# design.net
KiCad netlist of a schematic drawn in Altium Designer
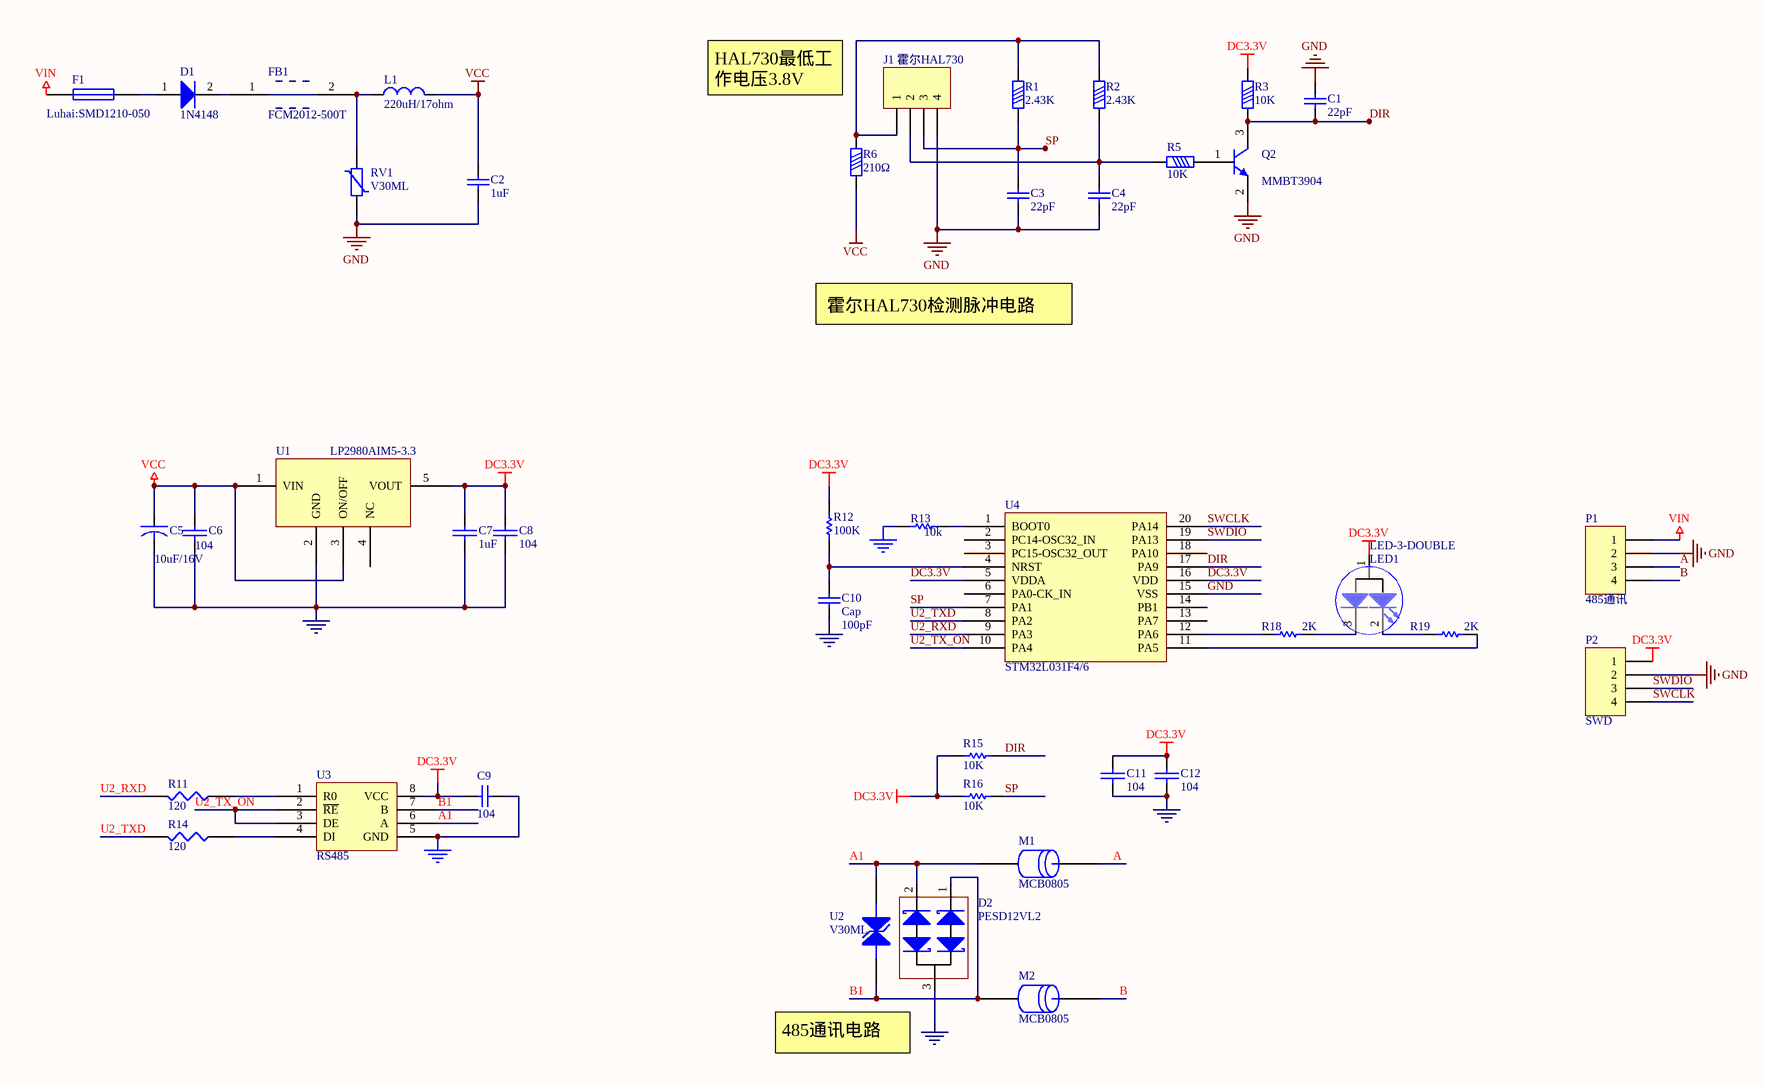
[diagram p0: 二合一正反转(改).SchDoc]

(export (version "E")
  (design (tool "Eeschema 10.0.6"))
  (components
    (comp (ref "C1")
      (value "22pF")
      (footprint "0603C")
      (description "Polarized Capacitor (Radial)")
      (fields (field (name "Comment") "Cap Chip 0603") (field (name "PUBLISHER") "Altium Limited"))
      (libsource (lib "EButterflyIntegratedLibrary") (part "Cap Chip 0603"))
    )
    (comp (ref "C2")
      (value "1uF")
      (footprint "0805C")
      (description "Polarized Capacitor (Radial)")
      (fields (field (name "PUBLISHER") "Altium Limited"))
      (libsource (lib "EButterflyIntegratedLibrary") (part "Cap Chip 0805"))
    )
    (comp (ref "C3")
      (value "22pF")
      (footprint "0603C")
      (description "Polarized Capacitor (Radial)")
      (fields (field (name "Comment") "Cap Chip 0603") (field (name "PUBLISHER") "Altium Limited"))
      (libsource (lib "EButterflyIntegratedLibrary") (part "Cap Chip 0603"))
    )
    (comp (ref "C4")
      (value "22pF")
      (footprint "0603C")
      (description "Polarized Capacitor (Radial)")
      (fields (field (name "Comment") "Cap Chip 0603") (field (name "PUBLISHER") "Altium Limited"))
      (libsource (lib "EButterflyIntegratedLibrary") (part "Cap Chip 0603"))
    )
    (comp (ref "C5")
      (value "10uF/16V")
      (footprint "A3216")
      (description "Capacitor")
      (libsource (lib "*") (part "CAPACITOR"))
    )
    (comp (ref "C6")
      (value "104")
      (footprint "0603C")
      (description "Capacitor")
      (libsource (lib "*") (part "CAP"))
    )
    (comp (ref "C7")
      (value "1uF")
      (footprint "0603C")
      (description "Capacitor")
      (libsource (lib "*") (part "CAP"))
    )
    (comp (ref "C8")
      (value "104")
      (footprint "0603C")
      (description "Capacitor")
      (libsource (lib "*") (part "CAP"))
    )
    (comp (ref "C9")
      (value "104")
      (footprint "0603C")
      (description "Capacitor")
      (fields (field (name "PUBLISHER") "*"))
      (libsource (lib "*") (part "Cap"))
    )
    (comp (ref "C10")
      (value "Cap")
      (footprint "0603C")
      (description "Capacitor")
      (fields (field (name "ALTIUM_VALUE") "100pF") (field (name "PUBLISHER") "Altium Limited"))
      (libsource (lib "Miscellaneous Devices") (part "Cap"))
    )
    (comp (ref "C11")
      (value "104")
      (footprint "0603C")
      (description "Capacitor")
      (libsource (lib "*") (part "CAP"))
    )
    (comp (ref "C12")
      (value "104")
      (footprint "0603C")
      (description "Capacitor")
      (libsource (lib "*") (part "CAP"))
    )
    (comp (ref "D1")
      (value "1N4148")
      (footprint "1N4148")
      (libsource (lib "Integrated_Library1") (part "1N4148"))
    )
    (comp (ref "D2") (value "PESD12VL2") (footprint "SOT23") (libsource (lib "lewis lib") (part "TVS")))
    (comp (ref "F1")
      (value "Luhai:SMD1210-050")
      (footprint "1210R")
      (description "Fuse")
      (fields (field (name "PUBLISHER") "Altium Limited"))
      (libsource (lib "Miscellaneous Devices") (part "Fuse 1"))
    )
    (comp (ref "FB1")
      (value "FCM2012-500T")
      (footprint "FB")
      (libsource (lib "Integrated_Library1") (part "FCM2012-500T"))
    )
    (comp (ref "J1")
      (value "霍尔HAL730")
      (footprint "HDR1X4")
      (description "Header, 4-Pin")
      (fields (field (name "PUBLISHER") "Altium Limited"))
      (libsource (lib "EButterflyIntegratedLibrary") (part "Header 4"))
    )
    (comp (ref "L1")
      (value "220uH/17ohm")
      (footprint "220uH/17ohm")
      (libsource (lib "Integrated_Library1") (part "220uH/17ohm"))
    )
    (comp (ref "LED1")
      (value "LED-3-DOUBLE")
      (footprint "LED-R3-H5-DOUBLE")
      (libsource (lib "Integrated_Library1") (part "DOUB-LED"))
    )
    (comp (ref "M1")
      (value "MCB0805")
      (footprint "0805F")
      (description "magnetic bead")
      (libsource (lib "lewis lib") (part "MAGNETIC BEAD"))
    )
    (comp (ref "M2")
      (value "MCB0805")
      (footprint "0805F")
      (description "magnetic bead")
      (libsource (lib "lewis lib") (part "MAGNETIC BEAD"))
    )
    (comp (ref "P1")
      (value "485通讯")
      (footprint "HDR1X4")
      (description "Header, 4-Pin, Right Angle")
      (fields (field (name "PUBLISHER") "Altium Limited"))
      (libsource (lib "Miscellaneous Connectors") (part "Header 4H"))
    )
    (comp (ref "P2")
      (value "SWD")
      (footprint "MHDR1X4")
      (description "Header, 4-Pin")
      (fields (field (name "PUBLISHER") "Altium Limited"))
      (libsource (lib "Miscellaneous Connectors") (part "Header 4"))
    )
    (comp (ref "Q2")
      (value "MMBT3904")
      (footprint "MMBT3904")
      (libsource (lib "Integrated_Library1") (part "MMBT3904"))
    )
    (comp (ref "R1")
      (value "2.43K")
      (footprint "0603C")
      (description "Resistor")
      (fields (field (name "Comment") "Resistor Chip 0603") (field (name "PUBLISHER") "Altium Limited"))
      (libsource (lib "EButterflyIntegratedLibrary") (part "Resistor Chip 0603"))
    )
    (comp (ref "R2")
      (value "2.43K")
      (footprint "0603C")
      (description "Resistor")
      (fields (field (name "Comment") "Resistor Chip 0603") (field (name "PUBLISHER") "Altium Limited"))
      (libsource (lib "EButterflyIntegratedLibrary") (part "Resistor Chip 0603"))
    )
    (comp (ref "R3")
      (value "10K")
      (footprint "0603C")
      (description "Resistor")
      (fields (field (name "Comment") "Resistor Chip 0603") (field (name "PUBLISHER") "Altium Limited"))
      (libsource (lib "EButterflyIntegratedLibrary") (part "Resistor Chip 0603"))
    )
    (comp (ref "R5")
      (value "10K")
      (footprint "0603C")
      (description "Resistor")
      (fields (field (name "Comment") "Resistor Chip 0603") (field (name "PUBLISHER") "Altium Limited"))
      (libsource (lib "") (part "Resistor Chip 0603_2"))
    )
    (comp (ref "R6")
      (value "210Ω")
      (footprint "0603C")
      (description "Resistor")
      (fields (field (name "Comment") "Resistor Chip 0603") (field (name "PUBLISHER") "Altium Limited"))
      (libsource (lib "") (part "Resistor Chip 0603_1"))
    )
    (comp (ref "R11") (value "120") (footprint "0603R") (libsource (lib "*") (part "RES1")))
    (comp (ref "R12")
      (value "100K")
      (footprint "0603R")
      (description "Resistor")
      (fields (field (name "PUBLISHER") "Altium Limited"))
      (libsource (lib "Miscellaneous Devices") (part "Res1"))
    )
    (comp (ref "R13")
      (value "10k")
      (footprint "0603R")
      (description "Resistor")
      (fields (field (name "PUBLISHER") "Altium Limited"))
      (libsource (lib "Miscellaneous Devices") (part "Res1"))
    )
    (comp (ref "R14") (value "120") (footprint "0603R") (libsource (lib "*") (part "RES1")))
    (comp (ref "R15")
      (value "10K")
      (footprint "0603R")
      (description "Resistor")
      (fields (field (name "PUBLISHER") "Altium Limited"))
      (libsource (lib "Miscellaneous Devices") (part "Res1"))
    )
    (comp (ref "R16")
      (value "10K")
      (footprint "0603R")
      (description "Resistor")
      (fields (field (name "PUBLISHER") "Altium Limited"))
      (libsource (lib "Miscellaneous Devices") (part "Res1"))
    )
    (comp (ref "R18")
      (value "2K")
      (footprint "0603R")
      (description "Resistor")
      (fields (field (name "PUBLISHER") "Altium Limited"))
      (libsource (lib "Miscellaneous Devices") (part "Res1"))
    )
    (comp (ref "R19")
      (value "2K")
      (footprint "0603R")
      (description "Resistor")
      (fields (field (name "PUBLISHER") "Altium Limited"))
      (libsource (lib "Miscellaneous Devices") (part "Res1"))
    )
    (comp (ref "RV1") (value "V30ML") (footprint "RV") (libsource (lib "Integrated_Library1") (part "V30ML")))
    (comp (ref "U1")
      (value "LP2980AIM5-3.3")
      (footprint "SOT23-5")
      (libsource (lib "lewis lib") (part "LP2980AIM5-3.3"))
    )
    (comp (ref "U2") (value "V30ML") (footprint "0805C-E") (libsource (lib "*") (part "V30ML")))
    (comp (ref "U3") (value "RS485") (footprint "SOP8") (libsource (lib "*") (part "RS485")))
    (comp (ref "U4")
      (value "STM32L031F4/6")
      (footprint "TSSOP20")
      (libsource (lib "lewis lib") (part "STM32L031F4/6"))
    )
  )
  (nets
    (net (code "1") (name "/A") (class "Default")
      (node (ref "M1") (pin "2") (pintype "passive"))
      (node (ref "P1") (pin "3") (pinfunction "3_3") (pintype "passive"))
    )
    (net (code "2") (name "/A1") (class "Default")
      (node (ref "D2") (pin "2") (pinfunction "2_2") (pintype "passive"))
      (node (ref "M1") (pin "1") (pintype "passive"))
      (node (ref "U2") (pin "2") (pinfunction "2_2") (pintype "passive"))
      (node (ref "U3") (pin "6") (pinfunction "A_6") (pintype "passive"))
    )
    (net (code "3") (name "/B") (class "Default")
      (node (ref "M2") (pin "2") (pintype "passive"))
      (node (ref "P1") (pin "4") (pinfunction "4_4") (pintype "passive"))
    )
    (net (code "4") (name "/B1") (class "Default")
      (node (ref "D2") (pin "1") (pinfunction "1_1") (pintype "passive"))
      (node (ref "M2") (pin "1") (pintype "passive"))
      (node (ref "U2") (pin "1") (pinfunction "1_1") (pintype "passive"))
      (node (ref "U3") (pin "7") (pinfunction "B_7") (pintype "passive"))
    )
    (net (code "5") (name "/DIR") (class "Default")
      (node (ref "C1") (pin "1") (pinfunction "1_1") (pintype "passive"))
      (node (ref "Q2") (pin "3") (pinfunction "C_3") (pintype "passive"))
      (node (ref "R15") (pin "1") (pinfunction "1_1") (pintype "passive"))
      (node (ref "R3") (pin "1") (pinfunction "1_1") (pintype "passive"))
      (node (ref "U4") (pin "17") (pinfunction "PA9_17") (pintype "passive"))
    )
    (net (code "6") (name "/SP") (class "Default")
      (node (ref "C3") (pin "2") (pinfunction "2_2") (pintype "passive"))
      (node (ref "J1") (pin "3") (pinfunction "3_3") (pintype "passive"))
      (node (ref "R1") (pin "1") (pinfunction "1_1") (pintype "passive"))
      (node (ref "R16") (pin "2") (pinfunction "2_2") (pintype "passive"))
      (node (ref "U4") (pin "7") (pinfunction "PA1_7") (pintype "passive"))
    )
    (net (code "7") (name "/SWCLK") (class "Default")
      (node (ref "P2") (pin "4") (pinfunction "4_4") (pintype "passive"))
      (node (ref "U4") (pin "20") (pinfunction "PA14_20") (pintype "passive"))
    )
    (net (code "8") (name "/SWDIO") (class "Default")
      (node (ref "P2") (pin "3") (pinfunction "3_3") (pintype "passive"))
      (node (ref "U4") (pin "19") (pinfunction "PA13_19") (pintype "passive"))
    )
    (net (code "9") (name "/U2_RXD") (class "Default")
      (node (ref "R11") (pin "2") (pinfunction "2_2") (pintype "passive"))
      (node (ref "U4") (pin "9") (pinfunction "PA3_9") (pintype "passive"))
    )
    (net (code "10") (name "/U2_TXD") (class "Default")
      (node (ref "R14") (pin "2") (pinfunction "2_2") (pintype "passive"))
      (node (ref "U4") (pin "8") (pinfunction "PA2_8") (pintype "passive"))
    )
    (net (code "11") (name "/U2_TX_ON") (class "Default")
      (node (ref "U3") (pin "2") (pinfunction "~{RE}_2") (pintype "passive"))
      (node (ref "U3") (pin "3") (pinfunction "DE_3") (pintype "passive"))
      (node (ref "U4") (pin "10") (pinfunction "PA4_10") (pintype "passive"))
    )
    (net (code "12") (name "DC3.3V") (class "Default")
      (node (ref "C11") (pin "1") (pinfunction "1_1") (pintype "passive"))
      (node (ref "C12") (pin "1") (pinfunction "1_1") (pintype "passive"))
      (node (ref "C7") (pin "1") (pinfunction "1_1") (pintype "passive"))
      (node (ref "C8") (pin "1") (pinfunction "1_1") (pintype "passive"))
      (node (ref "C9") (pin "1") (pinfunction "1_1") (pintype "passive"))
      (node (ref "LED1") (pin "1") (pinfunction "K_1") (pintype "passive"))
      (node (ref "P2") (pin "1") (pinfunction "1_1") (pintype "passive"))
      (node (ref "R12") (pin "1") (pinfunction "1_1") (pintype "passive"))
      (node (ref "R15") (pin "2") (pinfunction "2_2") (pintype "passive"))
      (node (ref "R16") (pin "1") (pinfunction "1_1") (pintype "passive"))
      (node (ref "R3") (pin "2") (pinfunction "2_2") (pintype "passive"))
      (node (ref "U1") (pin "5") (pinfunction "VOUT_5") (pintype "passive"))
      (node (ref "U3") (pin "8") (pinfunction "VCC_8") (pintype "passive"))
      (node (ref "U4") (pin "16") (pinfunction "VDD_16") (pintype "passive"))
      (node (ref "U4") (pin "5") (pinfunction "VDDA_5") (pintype "passive"))
    )
    (net (code "13") (name "GND") (class "Default")
      (node (ref "C1") (pin "2") (pinfunction "2_2") (pintype "passive"))
      (node (ref "C10") (pin "1") (pinfunction "1_1") (pintype "passive"))
      (node (ref "C11") (pin "2") (pinfunction "2_2") (pintype "passive"))
      (node (ref "C12") (pin "2") (pinfunction "2_2") (pintype "passive"))
      (node (ref "C2") (pin "1") (pinfunction "1_1") (pintype "passive"))
      (node (ref "C3") (pin "1") (pinfunction "1_1") (pintype "passive"))
      (node (ref "C4") (pin "1") (pinfunction "1_1") (pintype "passive"))
      (node (ref "C5") (pin "2") (pinfunction "2_2") (pintype "passive"))
      (node (ref "C6") (pin "2") (pinfunction "2_2") (pintype "passive"))
      (node (ref "C7") (pin "2") (pinfunction "2_2") (pintype "passive"))
      (node (ref "C8") (pin "2") (pinfunction "2_2") (pintype "passive"))
      (node (ref "C9") (pin "2") (pinfunction "2_2") (pintype "passive"))
      (node (ref "D2") (pin "3") (pinfunction "3_3") (pintype "passive"))
      (node (ref "J1") (pin "4") (pinfunction "4_4") (pintype "passive"))
      (node (ref "P1") (pin "2") (pinfunction "2_2") (pintype "passive"))
      (node (ref "P2") (pin "2") (pinfunction "2_2") (pintype "passive"))
      (node (ref "Q2") (pin "2") (pinfunction "E_2") (pintype "passive"))
      (node (ref "R13") (pin "2") (pinfunction "2_2") (pintype "passive"))
      (node (ref "RV1") (pin "1") (pinfunction "1_1") (pintype "passive"))
      (node (ref "U1") (pin "2") (pinfunction "GND_2") (pintype "passive"))
      (node (ref "U3") (pin "5") (pinfunction "GND_5") (pintype "passive"))
      (node (ref "U4") (pin "15") (pinfunction "VSS_15") (pintype "passive"))
    )
    (net (code "14") (name "Net-(C4-Pad2)") (class "Default")
      (node (ref "C4") (pin "2") (pinfunction "2_2") (pintype "passive"))
      (node (ref "J1") (pin "2") (pinfunction "2_2") (pintype "passive"))
      (node (ref "R2") (pin "1") (pinfunction "1_1") (pintype "passive"))
      (node (ref "R5") (pin "2") (pinfunction "2_2") (pintype "passive"))
    )
    (net (code "15") (name "Net-(D1-A)") (class "Default")
      (node (ref "D1") (pin "1") (pinfunction "A_1") (pintype "passive"))
      (node (ref "F1") (pin "2") (pinfunction "2_2") (pintype "passive"))
    )
    (net (code "16") (name "Net-(D1-K)") (class "Default")
      (node (ref "D1") (pin "2") (pinfunction "K_2") (pintype "passive"))
      (node (ref "FB1") (pin "1") (pinfunction "1_1") (pintype "passive"))
    )
    (net (code "17") (name "Net-(FB1-Pad2)") (class "Default")
      (node (ref "FB1") (pin "2") (pinfunction "2_2") (pintype "passive"))
      (node (ref "L1") (pin "1") (pinfunction "1_1") (pintype "passive"))
      (node (ref "RV1") (pin "2") (pinfunction "2_2") (pintype "passive"))
    )
    (net (code "18") (name "Net-(J1-Pad1)") (class "Default")
      (node (ref "J1") (pin "1") (pinfunction "1_1") (pintype "passive"))
      (node (ref "R1") (pin "2") (pinfunction "2_2") (pintype "passive"))
      (node (ref "R2") (pin "2") (pinfunction "2_2") (pintype "passive"))
      (node (ref "R6") (pin "1") (pinfunction "1_1") (pintype "passive"))
    )
    (net (code "19") (name "Net-(LED1-A-Pad2)") (class "Default")
      (node (ref "LED1") (pin "2") (pinfunction "A_2") (pintype "passive"))
      (node (ref "R19") (pin "1") (pinfunction "1_1") (pintype "passive"))
    )
    (net (code "20") (name "Net-(LED1-A-Pad3)") (class "Default")
      (node (ref "LED1") (pin "3") (pinfunction "A_3") (pintype "passive"))
      (node (ref "R18") (pin "2") (pinfunction "2_2") (pintype "passive"))
    )
    (net (code "21") (name "Net-(Q2-B)") (class "Default")
      (node (ref "Q2") (pin "1") (pinfunction "B_1") (pintype "passive"))
      (node (ref "R5") (pin "1") (pinfunction "1_1") (pintype "passive"))
    )
    (net (code "22") (name "Net-(U3-DI)") (class "Default")
      (node (ref "R14") (pin "1") (pinfunction "1_1") (pintype "passive"))
      (node (ref "U3") (pin "4") (pinfunction "DI_4") (pintype "passive"))
    )
    (net (code "23") (name "Net-(U3-R0)") (class "Default")
      (node (ref "R11") (pin "1") (pinfunction "1_1") (pintype "passive"))
      (node (ref "U3") (pin "1") (pinfunction "R0_1") (pintype "passive"))
    )
    (net (code "24") (name "Net-(U4-BOOT0)") (class "Default")
      (node (ref "R13") (pin "1") (pinfunction "1_1") (pintype "passive"))
      (node (ref "U4") (pin "1") (pinfunction "BOOT0_1") (pintype "passive"))
    )
    (net (code "25") (name "Net-(U4-NRST)") (class "Default")
      (node (ref "C10") (pin "2") (pinfunction "2_2") (pintype "passive"))
      (node (ref "R12") (pin "2") (pinfunction "2_2") (pintype "passive"))
      (node (ref "U4") (pin "4") (pinfunction "NRST_4") (pintype "passive"))
    )
    (net (code "26") (name "Net-(U4-PA5)") (class "Default")
      (node (ref "R19") (pin "2") (pinfunction "2_2") (pintype "passive"))
      (node (ref "U4") (pin "11") (pinfunction "PA5_11") (pintype "passive"))
    )
    (net (code "27") (name "Net-(U4-PA6)") (class "Default")
      (node (ref "R18") (pin "1") (pinfunction "1_1") (pintype "passive"))
      (node (ref "U4") (pin "12") (pinfunction "PA6_12") (pintype "passive"))
    )
    (net (code "28") (name "VCC") (class "Default")
      (node (ref "C2") (pin "2") (pinfunction "2_2") (pintype "passive"))
      (node (ref "C5") (pin "1") (pinfunction "1_1") (pintype "passive"))
      (node (ref "C6") (pin "1") (pinfunction "1_1") (pintype "passive"))
      (node (ref "L1") (pin "2") (pinfunction "2_2") (pintype "passive"))
      (node (ref "R6") (pin "2") (pinfunction "2_2") (pintype "passive"))
      (node (ref "U1") (pin "1") (pinfunction "VIN_1") (pintype "passive"))
      (node (ref "U1") (pin "3") (pinfunction "ON/OFF_3") (pintype "passive"))
    )
    (net (code "29") (name "VIN") (class "Default")
      (node (ref "F1") (pin "1") (pinfunction "1_1") (pintype "passive"))
      (node (ref "P1") (pin "1") (pinfunction "1_1") (pintype "passive"))
    )
    (net (code "30") (name "unconnected-(U1-NC-Pad4)") (class "Default")
      (node (ref "U1") (pin "4") (pinfunction "NC_4") (pintype "passive"))
    )
    (net (code "31") (name "unconnected-(U4-PA0-CK_IN-Pad6)") (class "Default")
      (node (ref "U4") (pin "6") (pinfunction "PA0-CK_IN_6") (pintype "passive"))
    )
    (net (code "32") (name "unconnected-(U4-PA7-Pad13)") (class "Default")
      (node (ref "U4") (pin "13") (pinfunction "PA7_13") (pintype "passive"))
    )
    (net (code "33") (name "unconnected-(U4-PA10-Pad18)") (class "Default")
      (node (ref "U4") (pin "18") (pinfunction "PA10_18") (pintype "passive"))
    )
    (net (code "34") (name "unconnected-(U4-PB1-Pad14)") (class "Default")
      (node (ref "U4") (pin "14") (pinfunction "PB1_14") (pintype "passive"))
    )
    (net (code "35") (name "unconnected-(U4-PC14-OSC32_IN-Pad2)") (class "Default")
      (node (ref "U4") (pin "2") (pinfunction "PC14-OSC32_IN_2") (pintype "passive"))
    )
    (net (code "36") (name "unconnected-(U4-PC15-OSC32_OUT-Pad3)") (class "Default")
      (node (ref "U4") (pin "3") (pinfunction "PC15-OSC32_OUT_3") (pintype "passive"))
    )
  )
)
